# Micro.net
KiCad netlist of a schematic drawn in Altium Designer
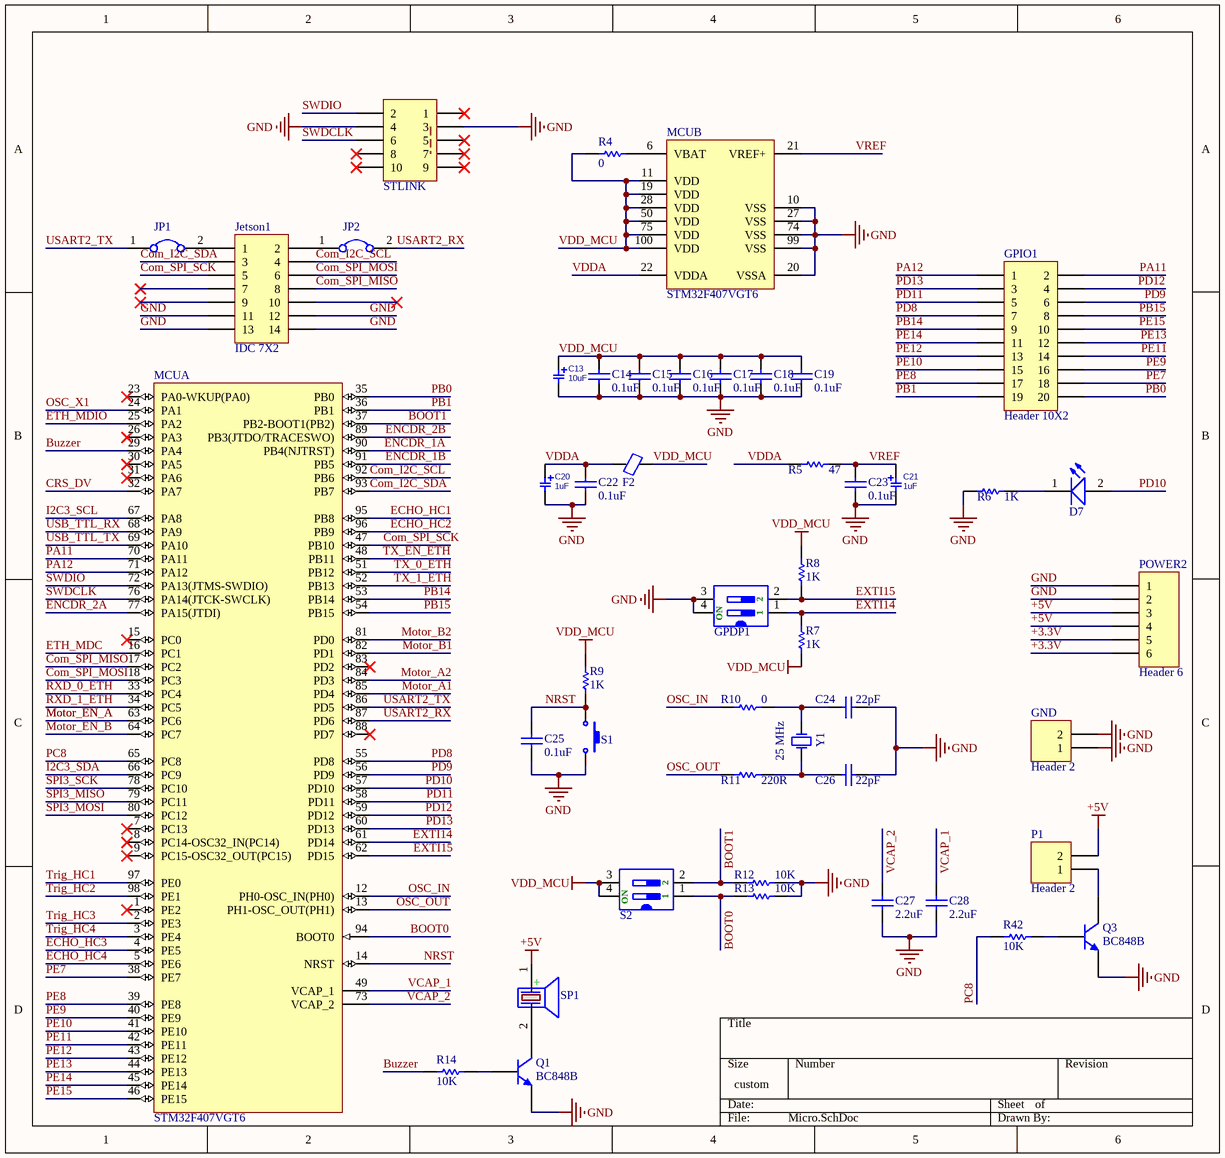
[diagram p0: Micro.SchDoc]

(export (version "E")
  (design (tool "Eeschema 10.0.6"))
  (components
    (comp (ref "C13")
      (value "10uF")
      (footprint "C_TN_6032")
      (description "CAP, SMD, TAN,")
      (libsource (lib "Passive") (part "CAP_SMD_TAN"))
    )
    (comp (ref "C14")
      (value "0.1uF")
      (footprint "CAPC3413X12N")
      (description "CAP 0805")
      (fields (field (name "DESIGNER") "Abbas Basereh"))
      (libsource (lib "Altium") (part "CAP SMD 0805"))
    )
    (comp (ref "C15")
      (value "0.1uF")
      (footprint "CAPC3413X12N")
      (description "CAP 0805")
      (fields (field (name "DESIGNER") "Abbas Basereh"))
      (libsource (lib "Altium") (part "CAP SMD 0805"))
    )
    (comp (ref "C16")
      (value "0.1uF")
      (footprint "CAPC3413X12N")
      (description "CAP 0805")
      (fields (field (name "DESIGNER") "Abbas Basereh"))
      (libsource (lib "Altium") (part "CAP SMD 0805"))
    )
    (comp (ref "C17")
      (value "0.1uF")
      (footprint "CAPC3413X12N")
      (description "CAP 0805")
      (fields (field (name "DESIGNER") "Abbas Basereh"))
      (libsource (lib "Altium") (part "CAP SMD 0805"))
    )
    (comp (ref "C18")
      (value "0.1uF")
      (footprint "CAPC3413X12N")
      (description "CAP 0805")
      (fields (field (name "DESIGNER") "Abbas Basereh"))
      (libsource (lib "Altium") (part "CAP SMD 0805"))
    )
    (comp (ref "C19")
      (value "0.1uF")
      (footprint "CAPC3413X12N")
      (description "CAP 0805")
      (fields (field (name "DESIGNER") "Abbas Basereh"))
      (libsource (lib "Altium") (part "CAP SMD 0805"))
    )
    (comp (ref "C20")
      (value "1uF")
      (footprint "C_TN_6032")
      (description "CAP, SMD, TAN,")
      (libsource (lib "Passive") (part "CAP_SMD_TAN"))
    )
    (comp (ref "C21")
      (value "1uF")
      (footprint "C_TN_6032")
      (description "CAP, SMD, TAN,")
      (libsource (lib "Passive") (part "CAP_SMD_TAN"))
    )
    (comp (ref "C22")
      (value "0.1uF")
      (footprint "CAPC3413X12N")
      (description "CAP 0805")
      (fields (field (name "DESIGNER") "Abbas Basereh"))
      (libsource (lib "Altium") (part "CAP SMD 0805"))
    )
    (comp (ref "C23")
      (value "0.1uF")
      (footprint "CAPC3413X12N")
      (description "CAP 0805")
      (fields (field (name "DESIGNER") "Abbas Basereh"))
      (libsource (lib "Altium") (part "CAP SMD 0805"))
    )
    (comp (ref "C24")
      (value "22pF")
      (footprint "CAPC3413X12N")
      (description "CAP 0805")
      (fields (field (name "DESIGNER") "Abbas Basereh"))
      (libsource (lib "Altium") (part "CAP SMD 0805"))
    )
    (comp (ref "C25")
      (value "0.1uF")
      (footprint "CAPC3413X12N")
      (description "CAP 0805")
      (fields (field (name "DESIGNER") "Abbas Basereh"))
      (libsource (lib "Altium") (part "CAP SMD 0805"))
    )
    (comp (ref "C26")
      (value "22pF")
      (footprint "CAPC3413X12N")
      (description "CAP 0805")
      (fields (field (name "DESIGNER") "Abbas Basereh"))
      (libsource (lib "Altium") (part "CAP SMD 0805"))
    )
    (comp (ref "C27")
      (value "2.2uF")
      (footprint "CAPC3413X12N")
      (description "CAP 0805")
      (fields (field (name "DESIGNER") "Abbas Basereh"))
      (libsource (lib "Altium") (part "CAP SMD 0805"))
    )
    (comp (ref "C28")
      (value "2.2uF")
      (footprint "CAPC3413X12N")
      (description "CAP 0805")
      (fields (field (name "DESIGNER") "Abbas Basereh"))
      (libsource (lib "Altium") (part "CAP SMD 0805"))
    )
    (comp (ref "D7")
      (value "LED SMD PACKAGE")
      (footprint "LED_SMD_0805")
      (description "SMD Mono-color Chip LED Waterclear")
      (fields (field (name "PART NUMBER") "150080BS75000") (field (name "PUBLISHER") "Ali Hafizi"))
      (libsource (lib "Altium") (part "LED SMD PACKAGE"))
    )
    (comp (ref "F2")
      (value "Ferrite Bead SMD")
      (footprint "FB0805")
      (fields (field (name "DESIGNER") "Ali Hafizi"))
      (libsource (lib "Altium") (part "Ferrite Bead SMD Package"))
    )
    (comp (ref "GND")
      (value "Header 2")
      (footprint "HDR1X2")
      (description "Header, 2-Pin")
      (fields (field (name "PUBLISHER") "Altium Limited"))
      (libsource (lib "Altium") (part "Header 2"))
    )
    (comp (ref "GPDP1")
      (value "SW_DIP_02")
      (footprint "SMV_DIP_CTS-219-02")
      (libsource (lib "SJ Switches") (part "SW_DIP_02"))
    )
    (comp (ref "GPIO1")
      (value "Header 10X2")
      (footprint "HDR2X10")
      (description "Header, 10-Pin, Dual row")
      (fields (field (name "PUBLISHER") "Altium Limited"))
      (libsource (lib "Altium") (part "Header 10X2"))
    )
    (comp (ref "Jetson1")
      (value "IDC 7X2")
      (footprint "IDC 7X2:IDC 7X2")
      (libsource (lib "IDC 7X2") (part "IDC 7X2"))
    )
    (comp (ref "JP1")
      (value "Jumper")
      (footprint "Jumper Small - 2.54 - GRAY")
      (libsource (lib "Altium") (part "Jumper"))
    )
    (comp (ref "JP2")
      (value "Jumper")
      (footprint "Jumper Small - 2.54 - GRAY")
      (libsource (lib "Altium") (part "Jumper"))
    )
    (comp (ref "MCU")
      (value "STM32F407VGT6")
      (footprint "STM-LQFP100_N")
      (fields (field (name "MANUFACTURER") "STMicroelectronics"))
      (libsource (lib "STMicroelectronics STM32 F4") (part "STM32F407VGT6"))
    )
    (comp (ref "P1")
      (value "Header 2")
      (footprint "HDR1X2")
      (description "Header, 2-Pin")
      (fields (field (name "PUBLISHER") "Altium Limited"))
      (libsource (lib "Altium") (part "Header 2"))
    )
    (comp (ref "POWER2")
      (value "Header 6")
      (footprint "HDR1X6")
      (description "Header, 6-Pin")
      (fields (field (name "PUBLISHER") "Altium Limited"))
      (libsource (lib "Altium") (part "Header 6"))
    )
    (comp (ref "Q1")
      (value "BC848B")
      (footprint "SOT23_L")
      (description "NPN General-purpose Transistor")
      (fields (field (name "PUBLISHER") "Abbas Basereh"))
      (libsource (lib "Altium") (part "BC848B"))
    )
    (comp (ref "Q3")
      (value "BC848B")
      (footprint "SOT23_L")
      (description "NPN General-purpose Transistor")
      (fields (field (name "PUBLISHER") "Abbas Basereh"))
      (libsource (lib "Altium") (part "BC848B"))
    )
    (comp (ref "R4")
      (value "0")
      (footprint "RESC3413X04N")
      (description "RES 0805")
      (fields (field (name "DESIGNER") "Abbas Basereh"))
      (libsource (lib "Altium") (part "RES 0805 0.125W"))
    )
    (comp (ref "R5")
      (value "47")
      (footprint "RESC3413X04N")
      (description "RES 0805")
      (fields (field (name "DESIGNER") "Abbas Basereh"))
      (libsource (lib "Altium") (part "RES 0805 0.125W"))
    )
    (comp (ref "R6")
      (value "1K")
      (footprint "RESC3413X04N")
      (description "RES 0805")
      (fields (field (name "DESIGNER") "Abbas Basereh"))
      (libsource (lib "Altium") (part "RES 0805 0.125W"))
    )
    (comp (ref "R7")
      (value "1K")
      (footprint "RESC3413X04N")
      (description "RES 0805")
      (fields (field (name "DESIGNER") "Abbas Basereh"))
      (libsource (lib "Altium") (part "RES 0805 0.125W"))
    )
    (comp (ref "R8")
      (value "1K")
      (footprint "RESC3413X04N")
      (description "RES 0805")
      (fields (field (name "DESIGNER") "Abbas Basereh"))
      (libsource (lib "Altium") (part "RES 0805 0.125W"))
    )
    (comp (ref "R9")
      (value "1K")
      (footprint "RESC3413X04N")
      (description "RES 0805")
      (fields (field (name "DESIGNER") "Abbas Basereh"))
      (libsource (lib "Altium") (part "RES 0805 0.125W"))
    )
    (comp (ref "R10")
      (value "0")
      (footprint "RESC3413X04N")
      (description "RES 0805")
      (fields (field (name "DESIGNER") "Abbas Basereh"))
      (libsource (lib "Altium") (part "RES 0805 0.125W"))
    )
    (comp (ref "R11")
      (value "220R")
      (footprint "RESC3413X04N")
      (description "RES 0805")
      (fields (field (name "DESIGNER") "Abbas Basereh"))
      (libsource (lib "Altium") (part "RES 0805 0.125W"))
    )
    (comp (ref "R12")
      (value "10K")
      (footprint "RESC3413X04N")
      (description "RES 0805")
      (fields (field (name "DESIGNER") "Abbas Basereh"))
      (libsource (lib "Altium") (part "RES 0805 0.125W"))
    )
    (comp (ref "R13")
      (value "10K")
      (footprint "RESC3413X04N")
      (description "RES 0805")
      (fields (field (name "DESIGNER") "Abbas Basereh"))
      (libsource (lib "Altium") (part "RES 0805 0.125W"))
    )
    (comp (ref "R14")
      (value "10K")
      (footprint "RES0805_(2012X06L)")
      (description "TOTAL SMD RESISTOR PACK")
      (fields (field (name "DESIGNER") "Abbas Basereh"))
      (libsource (lib "Altium") (part "RES SMD PACKAGE"))
    )
    (comp (ref "R42")
      (value "10K")
      (footprint "RES0805_(2012X06L)")
      (description "TOTAL SMD RESISTOR PACK")
      (fields (field (name "DESIGNER") "Abbas Basereh"))
      (libsource (lib "Altium") (part "RES SMD PACKAGE"))
    )
    (comp (ref "S1")
      (value "Switch PB")
      (footprint "SW-PB")
      (description "Push Button Switch")
      (libsource (lib "Altium") (part "Switch PB"))
    )
    (comp (ref "S2")
      (value "SW_DIP_02")
      (footprint "SMV_DIP_CTS-219-02")
      (libsource (lib "SJ Switches") (part "SW_DIP_02"))
    )
    (comp (ref "SP1")
      (value "~")
      (footprint "BUZZER 7.62mm DC")
      (description "PIEZO BUZZER ACTIVE")
      (fields (field (name "DESIGNER") "Abbas Basereh") (field (name "PUBLISHER") "Abbas Basereh"))
      (libsource (lib "Altium") (part "PIEZO BUZZER"))
    )
    (comp (ref "STLINK")
      (value "CONNECTOR_IDC_5X2")
      (footprint "IDC2.54-10PIN")
      (description "IDC, 5-Pin, Dual row")
      (fields
        (field (name "MANUFACTURER") "CHINA")
        (field (name "PUBLISHER") "ABBAS BASEREH")
        (field (name "DESIGNER") "ABBAS BASEREH")
      )
      (libsource (lib "Altium") (part "IDC 5X2"))
    )
    (comp (ref "Y1")
      (value "25 MHz")
      (footprint "Crystal SMD")
      (description "XTAL Crystal")
      (fields (field (name "DESIGNER") "ABBAS BASEREH"))
      (libsource (lib "Altium") (part "XTAL"))
    )
  )
  (nets
    (net (code "1") (name "+5V") (class "Default")
      (node (ref "P1") (pin "2") (pinfunction "2_2") (pintype "passive"))
      (node (ref "POWER2") (pin "3") (pinfunction "3_3") (pintype "passive"))
      (node (ref "POWER2") (pin "4") (pinfunction "4_4") (pintype "passive"))
      (node (ref "SP1") (pin "1") (pinfunction "+_1") (pintype "passive"))
    )
    (net (code "2") (name "/+3.3V") (class "Default")
      (node (ref "POWER2") (pin "5") (pinfunction "5_5") (pintype "passive"))
      (node (ref "POWER2") (pin "6") (pinfunction "6_6") (pintype "passive"))
    )
    (net (code "3") (name "/BOOT0") (class "Default")
      (node (ref "MCU") (pin "94") (pinfunction "BOOT0_94") (pintype "input"))
      (node (ref "R13") (pin "1") (pinfunction "1_1") (pintype "passive"))
      (node (ref "S2") (pin "1") (pinfunction "1_1") (pintype "passive"))
    )
    (net (code "4") (name "/BOOT1") (class "Default")
      (node (ref "MCU") (pin "37") (pinfunction "PB2-BOOT1(PB2)_37") (pintype "bidirectional"))
      (node (ref "R12") (pin "1") (pinfunction "1_1") (pintype "passive"))
      (node (ref "S2") (pin "2") (pinfunction "2_2") (pintype "passive"))
    )
    (net (code "5") (name "/Buzzer") (class "Default")
      (node (ref "MCU") (pin "29") (pinfunction "PA4_29") (pintype "bidirectional"))
      (node (ref "R14") (pin "1") (pinfunction "1_1") (pintype "passive"))
    )
    (net (code "6") (name "/CRS_DV") (class "Default")
      (node (ref "MCU") (pin "32") (pinfunction "PA7_32") (pintype "bidirectional"))
    )
    (net (code "7") (name "/Com_I2C_SCL") (class "Default")
      (node (ref "Jetson1") (pin "4") (pinfunction "4_4") (pintype "passive"))
      (node (ref "MCU") (pin "92") (pinfunction "PB6_92") (pintype "bidirectional"))
    )
    (net (code "8") (name "/Com_I2C_SDA") (class "Default")
      (node (ref "Jetson1") (pin "3") (pinfunction "3_3") (pintype "passive"))
      (node (ref "MCU") (pin "93") (pinfunction "PB7_93") (pintype "bidirectional"))
    )
    (net (code "9") (name "/Com_SPI_MISO") (class "Default")
      (node (ref "Jetson1") (pin "8") (pinfunction "8_8") (pintype "passive"))
      (node (ref "MCU") (pin "17") (pinfunction "PC2_17") (pintype "bidirectional"))
    )
    (net (code "10") (name "/Com_SPI_MOSI") (class "Default")
      (node (ref "Jetson1") (pin "6") (pinfunction "6_6") (pintype "passive"))
      (node (ref "MCU") (pin "18") (pinfunction "PC3_18") (pintype "bidirectional"))
    )
    (net (code "11") (name "/Com_SPI_SCK") (class "Default")
      (node (ref "Jetson1") (pin "5") (pinfunction "5_5") (pintype "passive"))
      (node (ref "MCU") (pin "47") (pinfunction "PB10_47") (pintype "bidirectional"))
    )
    (net (code "12") (name "/ECHO_HC1") (class "Default")
      (node (ref "MCU") (pin "95") (pinfunction "PB8_95") (pintype "bidirectional"))
    )
    (net (code "13") (name "/ECHO_HC2") (class "Default")
      (node (ref "MCU") (pin "96") (pinfunction "PB9_96") (pintype "bidirectional"))
    )
    (net (code "14") (name "/ECHO_HC3") (class "Default")
      (node (ref "MCU") (pin "4") (pinfunction "PE5_4") (pintype "bidirectional"))
    )
    (net (code "15") (name "/ECHO_HC4") (class "Default")
      (node (ref "MCU") (pin "5") (pinfunction "PE6_5") (pintype "bidirectional"))
    )
    (net (code "16") (name "/ENCDR_1A") (class "Default")
      (node (ref "MCU") (pin "90") (pinfunction "PB4(NJTRST)_90") (pintype "bidirectional"))
    )
    (net (code "17") (name "/ENCDR_1B") (class "Default")
      (node (ref "MCU") (pin "91") (pinfunction "PB5_91") (pintype "bidirectional"))
    )
    (net (code "18") (name "/ENCDR_2A") (class "Default")
      (node (ref "MCU") (pin "77") (pinfunction "PA15(JTDI)_77") (pintype "bidirectional"))
    )
    (net (code "19") (name "/ENCDR_2B") (class "Default")
      (node (ref "MCU") (pin "89") (pinfunction "PB3(JTDO/TRACESWO)_89") (pintype "bidirectional"))
    )
    (net (code "20") (name "/ETH_MDC") (class "Default")
      (node (ref "MCU") (pin "16") (pinfunction "PC1_16") (pintype "bidirectional"))
    )
    (net (code "21") (name "/ETH_MDIO") (class "Default")
      (node (ref "MCU") (pin "25") (pinfunction "PA2_25") (pintype "bidirectional"))
    )
    (net (code "22") (name "/EXTI14") (class "Default")
      (node (ref "GPDP1") (pin "1") (pinfunction "1_1") (pintype "passive"))
      (node (ref "MCU") (pin "61") (pinfunction "PD14_61") (pintype "bidirectional"))
      (node (ref "R7") (pin "2") (pinfunction "2_2") (pintype "passive"))
    )
    (net (code "23") (name "/EXTI15") (class "Default")
      (node (ref "GPDP1") (pin "2") (pinfunction "2_2") (pintype "passive"))
      (node (ref "MCU") (pin "62") (pinfunction "PD15_62") (pintype "bidirectional"))
      (node (ref "R8") (pin "2") (pinfunction "2_2") (pintype "passive"))
    )
    (net (code "24") (name "/I2C3_SCL") (class "Default")
      (node (ref "MCU") (pin "67") (pinfunction "PA8_67") (pintype "bidirectional"))
    )
    (net (code "25") (name "/I2C3_SDA") (class "Default")
      (node (ref "MCU") (pin "66") (pinfunction "PC9_66") (pintype "bidirectional"))
    )
    (net (code "26") (name "/Motor_A1") (class "Default")
      (node (ref "MCU") (pin "85") (pinfunction "PD4_85") (pintype "bidirectional"))
    )
    (net (code "27") (name "/Motor_A2") (class "Default")
      (node (ref "MCU") (pin "84") (pinfunction "PD3_84") (pintype "bidirectional"))
    )
    (net (code "28") (name "/Motor_B1") (class "Default")
      (node (ref "MCU") (pin "82") (pinfunction "PD1_82") (pintype "bidirectional"))
    )
    (net (code "29") (name "/Motor_B2") (class "Default")
      (node (ref "MCU") (pin "81") (pinfunction "PD0_81") (pintype "bidirectional"))
    )
    (net (code "30") (name "/Motor_EN_A") (class "Default")
      (node (ref "MCU") (pin "63") (pinfunction "PC6_63") (pintype "bidirectional"))
    )
    (net (code "31") (name "/Motor_EN_B") (class "Default")
      (node (ref "MCU") (pin "64") (pinfunction "PC7_64") (pintype "bidirectional"))
    )
    (net (code "32") (name "/NRST") (class "Default")
      (node (ref "C25") (pin "2") (pinfunction "2_2") (pintype "passive"))
      (node (ref "MCU") (pin "14") (pinfunction "NRST_14") (pintype "bidirectional"))
      (node (ref "R9") (pin "1") (pinfunction "1_1") (pintype "passive"))
      (node (ref "S1") (pin "1") (pinfunction "1_1") (pintype "passive"))
    )
    (net (code "33") (name "/OSC_IN") (class "Default")
      (node (ref "MCU") (pin "12") (pinfunction "PH0-OSC_IN(PH0)_12") (pintype "bidirectional"))
      (node (ref "R10") (pin "1") (pinfunction "1_1") (pintype "passive"))
    )
    (net (code "34") (name "/OSC_OUT") (class "Default")
      (node (ref "MCU") (pin "13") (pinfunction "PH1-OSC_OUT(PH1)_13") (pintype "bidirectional"))
      (node (ref "R11") (pin "1") (pinfunction "1_1") (pintype "passive"))
    )
    (net (code "35") (name "/OSC_X1") (class "Default")
      (node (ref "MCU") (pin "24") (pinfunction "PA1_24") (pintype "bidirectional"))
    )
    (net (code "36") (name "/PA11") (class "Default")
      (node (ref "GPIO1") (pin "2") (pinfunction "2_2") (pintype "passive"))
      (node (ref "MCU") (pin "70") (pinfunction "PA11_70") (pintype "bidirectional"))
    )
    (net (code "37") (name "/PA12") (class "Default")
      (node (ref "GPIO1") (pin "1") (pinfunction "1_1") (pintype "passive"))
      (node (ref "MCU") (pin "71") (pinfunction "PA12_71") (pintype "bidirectional"))
    )
    (net (code "38") (name "/PB0") (class "Default")
      (node (ref "GPIO1") (pin "20") (pinfunction "20_20") (pintype "passive"))
      (node (ref "MCU") (pin "35") (pinfunction "PB0_35") (pintype "bidirectional"))
    )
    (net (code "39") (name "/PB1") (class "Default")
      (node (ref "GPIO1") (pin "19") (pinfunction "19_19") (pintype "passive"))
      (node (ref "MCU") (pin "36") (pinfunction "PB1_36") (pintype "bidirectional"))
    )
    (net (code "40") (name "/PB14") (class "Default")
      (node (ref "GPIO1") (pin "9") (pinfunction "9_9") (pintype "passive"))
      (node (ref "MCU") (pin "53") (pinfunction "PB14_53") (pintype "bidirectional"))
    )
    (net (code "41") (name "/PB15") (class "Default")
      (node (ref "GPIO1") (pin "8") (pinfunction "8_8") (pintype "passive"))
      (node (ref "MCU") (pin "54") (pinfunction "PB15_54") (pintype "bidirectional"))
    )
    (net (code "42") (name "/PC8") (class "Default")
      (node (ref "MCU") (pin "65") (pinfunction "PC8_65") (pintype "bidirectional"))
      (node (ref "R42") (pin "1") (pinfunction "1_1") (pintype "passive"))
    )
    (net (code "43") (name "/PD8") (class "Default")
      (node (ref "GPIO1") (pin "7") (pinfunction "7_7") (pintype "passive"))
      (node (ref "MCU") (pin "55") (pinfunction "PD8_55") (pintype "bidirectional"))
    )
    (net (code "44") (name "/PD9") (class "Default")
      (node (ref "GPIO1") (pin "6") (pinfunction "6_6") (pintype "passive"))
      (node (ref "MCU") (pin "56") (pinfunction "PD9_56") (pintype "bidirectional"))
    )
    (net (code "45") (name "/PD10") (class "Default")
      (node (ref "D7") (pin "2") (pinfunction "A_2") (pintype "passive"))
      (node (ref "MCU") (pin "57") (pinfunction "PD10_57") (pintype "bidirectional"))
    )
    (net (code "46") (name "/PD11") (class "Default")
      (node (ref "GPIO1") (pin "5") (pinfunction "5_5") (pintype "passive"))
      (node (ref "MCU") (pin "58") (pinfunction "PD11_58") (pintype "bidirectional"))
    )
    (net (code "47") (name "/PD12") (class "Default")
      (node (ref "GPIO1") (pin "4") (pinfunction "4_4") (pintype "passive"))
      (node (ref "MCU") (pin "59") (pinfunction "PD12_59") (pintype "bidirectional"))
    )
    (net (code "48") (name "/PD13") (class "Default")
      (node (ref "GPIO1") (pin "3") (pinfunction "3_3") (pintype "passive"))
      (node (ref "MCU") (pin "60") (pinfunction "PD13_60") (pintype "bidirectional"))
    )
    (net (code "49") (name "/PE7") (class "Default")
      (node (ref "GPIO1") (pin "18") (pinfunction "18_18") (pintype "passive"))
      (node (ref "MCU") (pin "38") (pinfunction "PE7_38") (pintype "bidirectional"))
    )
    (net (code "50") (name "/PE8") (class "Default")
      (node (ref "GPIO1") (pin "17") (pinfunction "17_17") (pintype "passive"))
      (node (ref "MCU") (pin "39") (pinfunction "PE8_39") (pintype "bidirectional"))
    )
    (net (code "51") (name "/PE9") (class "Default")
      (node (ref "GPIO1") (pin "16") (pinfunction "16_16") (pintype "passive"))
      (node (ref "MCU") (pin "40") (pinfunction "PE9_40") (pintype "bidirectional"))
    )
    (net (code "52") (name "/PE10") (class "Default")
      (node (ref "GPIO1") (pin "15") (pinfunction "15_15") (pintype "passive"))
      (node (ref "MCU") (pin "41") (pinfunction "PE10_41") (pintype "bidirectional"))
    )
    (net (code "53") (name "/PE11") (class "Default")
      (node (ref "GPIO1") (pin "14") (pinfunction "14_14") (pintype "passive"))
      (node (ref "MCU") (pin "42") (pinfunction "PE11_42") (pintype "bidirectional"))
    )
    (net (code "54") (name "/PE12") (class "Default")
      (node (ref "GPIO1") (pin "13") (pinfunction "13_13") (pintype "passive"))
      (node (ref "MCU") (pin "43") (pinfunction "PE12_43") (pintype "bidirectional"))
    )
    (net (code "55") (name "/PE13") (class "Default")
      (node (ref "GPIO1") (pin "12") (pinfunction "12_12") (pintype "passive"))
      (node (ref "MCU") (pin "44") (pinfunction "PE13_44") (pintype "bidirectional"))
    )
    (net (code "56") (name "/PE14") (class "Default")
      (node (ref "GPIO1") (pin "11") (pinfunction "11_11") (pintype "passive"))
      (node (ref "MCU") (pin "45") (pinfunction "PE14_45") (pintype "bidirectional"))
    )
    (net (code "57") (name "/PE15") (class "Default")
      (node (ref "GPIO1") (pin "10") (pinfunction "10_10") (pintype "passive"))
      (node (ref "MCU") (pin "46") (pinfunction "PE15_46") (pintype "bidirectional"))
    )
    (net (code "58") (name "/RXD_0_ETH") (class "Default")
      (node (ref "MCU") (pin "33") (pinfunction "PC4_33") (pintype "bidirectional"))
    )
    (net (code "59") (name "/RXD_1_ETH") (class "Default")
      (node (ref "MCU") (pin "34") (pinfunction "PC5_34") (pintype "bidirectional"))
    )
    (net (code "60") (name "/SPI3_MISO") (class "Default")
      (node (ref "MCU") (pin "79") (pinfunction "PC11_79") (pintype "bidirectional"))
    )
    (net (code "61") (name "/SPI3_MOSI") (class "Default")
      (node (ref "MCU") (pin "80") (pinfunction "PC12_80") (pintype "bidirectional"))
    )
    (net (code "62") (name "/SPI3_SCK") (class "Default")
      (node (ref "MCU") (pin "78") (pinfunction "PC10_78") (pintype "bidirectional"))
    )
    (net (code "63") (name "/SWDCLK") (class "Default")
      (node (ref "MCU") (pin "76") (pinfunction "PA14(JTCK-SWCLK)_76") (pintype "bidirectional"))
      (node (ref "STLINK") (pin "6") (pinfunction "6_6") (pintype "passive"))
    )
    (net (code "64") (name "/SWDIO") (class "Default")
      (node (ref "MCU") (pin "72") (pinfunction "PA13(JTMS-SWDIO)_72") (pintype "bidirectional"))
      (node (ref "STLINK") (pin "2") (pinfunction "2_2") (pintype "passive"))
    )
    (net (code "65") (name "/TX_0_ETH") (class "Default")
      (node (ref "MCU") (pin "51") (pinfunction "PB12_51") (pintype "bidirectional"))
    )
    (net (code "66") (name "/TX_1_ETH") (class "Default")
      (node (ref "MCU") (pin "52") (pinfunction "PB13_52") (pintype "bidirectional"))
    )
    (net (code "67") (name "/TX_EN_ETH") (class "Default")
      (node (ref "MCU") (pin "48") (pinfunction "PB11_48") (pintype "bidirectional"))
    )
    (net (code "68") (name "/Trig_HC1") (class "Default")
      (node (ref "MCU") (pin "97") (pinfunction "PE0_97") (pintype "bidirectional"))
    )
    (net (code "69") (name "/Trig_HC2") (class "Default")
      (node (ref "MCU") (pin "98") (pinfunction "PE1_98") (pintype "bidirectional"))
    )
    (net (code "70") (name "/Trig_HC3") (class "Default")
      (node (ref "MCU") (pin "2") (pinfunction "PE3_2") (pintype "bidirectional"))
    )
    (net (code "71") (name "/Trig_HC4") (class "Default")
      (node (ref "MCU") (pin "3") (pinfunction "PE4_3") (pintype "bidirectional"))
    )
    (net (code "72") (name "/USART2_RX") (class "Default")
      (node (ref "JP2") (pin "2") (pinfunction "2_2") (pintype "passive"))
      (node (ref "MCU") (pin "87") (pinfunction "PD6_87") (pintype "bidirectional"))
    )
    (net (code "73") (name "/USART2_TX") (class "Default")
      (node (ref "JP1") (pin "1") (pinfunction "1_1") (pintype "passive"))
      (node (ref "MCU") (pin "86") (pinfunction "PD5_86") (pintype "bidirectional"))
    )
    (net (code "74") (name "/USB_TTL_RX") (class "Default")
      (node (ref "MCU") (pin "68") (pinfunction "PA9_68") (pintype "bidirectional"))
    )
    (net (code "75") (name "/USB_TTL_TX") (class "Default")
      (node (ref "MCU") (pin "69") (pinfunction "PA10_69") (pintype "bidirectional"))
    )
    (net (code "76") (name "/VCAP_1") (class "Default")
      (node (ref "C28") (pin "2") (pinfunction "2_2") (pintype "passive"))
      (node (ref "MCU") (pin "49") (pinfunction "VCAP_1_49") (pintype "power_in"))
    )
    (net (code "77") (name "/VCAP_2") (class "Default")
      (node (ref "C27") (pin "2") (pinfunction "2_2") (pintype "passive"))
      (node (ref "MCU") (pin "73") (pinfunction "VCAP_2_73") (pintype "power_in"))
    )
    (net (code "78") (name "/VDDA") (class "Default")
      (node (ref "C20") (pin "1") (pinfunction "1_1") (pintype "passive"))
      (node (ref "C22") (pin "2") (pinfunction "2_2") (pintype "passive"))
      (node (ref "F2") (pin "1") (pinfunction "1_1") (pintype "passive"))
      (node (ref "MCU") (pin "22") (pinfunction "VDDA_22") (pintype "power_in"))
      (node (ref "R5") (pin "1") (pinfunction "1_1") (pintype "passive"))
    )
    (net (code "79") (name "/VREF") (class "Default")
      (node (ref "C21") (pin "1") (pinfunction "1_1") (pintype "passive"))
      (node (ref "C23") (pin "2") (pinfunction "2_2") (pintype "passive"))
      (node (ref "MCU") (pin "21") (pinfunction "VREF+_21") (pintype "power_in"))
      (node (ref "R5") (pin "2") (pinfunction "2_2") (pintype "passive"))
    )
    (net (code "80") (name "GND") (class "Default")
      (node (ref "C13") (pin "2") (pinfunction "2_2") (pintype "passive"))
      (node (ref "C14") (pin "1") (pinfunction "1_1") (pintype "passive"))
      (node (ref "C15") (pin "1") (pinfunction "1_1") (pintype "passive"))
      (node (ref "C16") (pin "1") (pinfunction "1_1") (pintype "passive"))
      (node (ref "C17") (pin "1") (pinfunction "1_1") (pintype "passive"))
      (node (ref "C18") (pin "1") (pinfunction "1_1") (pintype "passive"))
      (node (ref "C19") (pin "1") (pinfunction "1_1") (pintype "passive"))
      (node (ref "C20") (pin "2") (pinfunction "2_2") (pintype "passive"))
      (node (ref "C21") (pin "2") (pinfunction "2_2") (pintype "passive"))
      (node (ref "C22") (pin "1") (pinfunction "1_1") (pintype "passive"))
      (node (ref "C23") (pin "1") (pinfunction "1_1") (pintype "passive"))
      (node (ref "C24") (pin "1") (pinfunction "1_1") (pintype "passive"))
      (node (ref "C25") (pin "1") (pinfunction "1_1") (pintype "passive"))
      (node (ref "C26") (pin "1") (pinfunction "1_1") (pintype "passive"))
      (node (ref "C27") (pin "1") (pinfunction "1_1") (pintype "passive"))
      (node (ref "C28") (pin "1") (pinfunction "1_1") (pintype "passive"))
      (node (ref "GND") (pin "1") (pinfunction "1_1") (pintype "passive"))
      (node (ref "GND") (pin "2") (pinfunction "2_2") (pintype "passive"))
      (node (ref "GPDP1") (pin "3") (pinfunction "3_3") (pintype "passive"))
      (node (ref "GPDP1") (pin "4") (pinfunction "4_4") (pintype "passive"))
      (node (ref "Jetson1") (pin "11") (pinfunction "11_11") (pintype "passive"))
      (node (ref "Jetson1") (pin "12") (pinfunction "12_12") (pintype "passive"))
      (node (ref "Jetson1") (pin "13") (pinfunction "13_13") (pintype "passive"))
      (node (ref "Jetson1") (pin "14") (pinfunction "14_14") (pintype "passive"))
      (node (ref "MCU") (pin "10") (pinfunction "VSS_10") (pintype "power_in"))
      (node (ref "MCU") (pin "20") (pinfunction "VSSA_20") (pintype "power_in"))
      (node (ref "MCU") (pin "27") (pinfunction "VSS_27") (pintype "power_in"))
      (node (ref "MCU") (pin "74") (pinfunction "VSS_74") (pintype "power_in"))
      (node (ref "MCU") (pin "99") (pinfunction "VSS_99") (pintype "power_in"))
      (node (ref "POWER2") (pin "1") (pinfunction "1_1") (pintype "passive"))
      (node (ref "POWER2") (pin "2") (pinfunction "2_2") (pintype "passive"))
      (node (ref "Q1") (pin "2") (pinfunction "E_2") (pintype "passive"))
      (node (ref "Q3") (pin "2") (pinfunction "E_2") (pintype "passive"))
      (node (ref "R12") (pin "2") (pinfunction "2_2") (pintype "passive"))
      (node (ref "R13") (pin "2") (pinfunction "2_2") (pintype "passive"))
      (node (ref "R6") (pin "1") (pinfunction "1_1") (pintype "passive"))
      (node (ref "S1") (pin "2") (pinfunction "2_2") (pintype "passive"))
      (node (ref "STLINK") (pin "3") (pinfunction "3_3") (pintype "passive"))
      (node (ref "STLINK") (pin "4") (pinfunction "4_4") (pintype "passive"))
    )
    (net (code "81") (name "Net-(D7-K)") (class "Default")
      (node (ref "D7") (pin "1") (pinfunction "K_1") (pintype "passive"))
      (node (ref "R6") (pin "2") (pinfunction "2_2") (pintype "passive"))
    )
    (net (code "82") (name "Net-(JP1-Pad2)") (class "Default")
      (node (ref "JP1") (pin "2") (pinfunction "2_2") (pintype "passive"))
      (node (ref "Jetson1") (pin "1") (pinfunction "1_1") (pintype "passive"))
    )
    (net (code "83") (name "Net-(JP2-Pad1)") (class "Default")
      (node (ref "JP2") (pin "1") (pinfunction "1_1") (pintype "passive"))
      (node (ref "Jetson1") (pin "2") (pinfunction "2_2") (pintype "passive"))
    )
    (net (code "84") (name "Net-(MCUB-VBAT)") (class "Default")
      (node (ref "MCU") (pin "6") (pinfunction "VBAT_6") (pintype "power_in"))
      (node (ref "R4") (pin "2") (pinfunction "2_2") (pintype "passive"))
    )
    (net (code "85") (name "Net-(Q1-B)") (class "Default")
      (node (ref "Q1") (pin "1") (pinfunction "B_1") (pintype "passive"))
      (node (ref "R14") (pin "2") (pinfunction "2_2") (pintype "passive"))
    )
    (net (code "86") (name "Net-(Q1-C)") (class "Default")
      (node (ref "Q1") (pin "3") (pinfunction "C_3") (pintype "passive"))
      (node (ref "SP1") (pin "2") (pinfunction "-_2") (pintype "passive"))
    )
    (net (code "87") (name "Net-(Q3-B)") (class "Default")
      (node (ref "Q3") (pin "1") (pinfunction "B_1") (pintype "passive"))
      (node (ref "R42") (pin "2") (pinfunction "2_2") (pintype "passive"))
    )
    (net (code "88") (name "Net-(Q3-C)") (class "Default")
      (node (ref "P1") (pin "1") (pinfunction "1_1") (pintype "passive"))
      (node (ref "Q3") (pin "3") (pinfunction "C_3") (pintype "passive"))
    )
    (net (code "89") (name "Net-(Y1-OSC1)") (class "Default")
      (node (ref "C26") (pin "2") (pinfunction "2_2") (pintype "passive"))
      (node (ref "R11") (pin "2") (pinfunction "2_2") (pintype "passive"))
      (node (ref "Y1") (pin "1") (pinfunction "OSC1_1") (pintype "passive"))
    )
    (net (code "90") (name "Net-(Y1-OSC2)") (class "Default")
      (node (ref "C24") (pin "2") (pinfunction "2_2") (pintype "passive"))
      (node (ref "R10") (pin "2") (pinfunction "2_2") (pintype "passive"))
      (node (ref "Y1") (pin "2") (pinfunction "OSC2_2") (pintype "passive"))
    )
    (net (code "91") (name "VDD_MCU") (class "Default")
      (node (ref "C13") (pin "1") (pinfunction "1_1") (pintype "passive"))
      (node (ref "C14") (pin "2") (pinfunction "2_2") (pintype "passive"))
      (node (ref "C15") (pin "2") (pinfunction "2_2") (pintype "passive"))
      (node (ref "C16") (pin "2") (pinfunction "2_2") (pintype "passive"))
      (node (ref "C17") (pin "2") (pinfunction "2_2") (pintype "passive"))
      (node (ref "C18") (pin "2") (pinfunction "2_2") (pintype "passive"))
      (node (ref "C19") (pin "2") (pinfunction "2_2") (pintype "passive"))
      (node (ref "F2") (pin "2") (pinfunction "2_2") (pintype "passive"))
      (node (ref "MCU") (pin "100") (pinfunction "VDD_100") (pintype "power_in"))
      (node (ref "MCU") (pin "11") (pinfunction "VDD_11") (pintype "power_in"))
      (node (ref "MCU") (pin "19") (pinfunction "VDD_19") (pintype "power_in"))
      (node (ref "MCU") (pin "28") (pinfunction "VDD_28") (pintype "power_in"))
      (node (ref "MCU") (pin "50") (pinfunction "VDD_50") (pintype "power_in"))
      (node (ref "MCU") (pin "75") (pinfunction "VDD_75") (pintype "power_in"))
      (node (ref "R4") (pin "1") (pinfunction "1_1") (pintype "passive"))
      (node (ref "R7") (pin "1") (pinfunction "1_1") (pintype "passive"))
      (node (ref "R8") (pin "1") (pinfunction "1_1") (pintype "passive"))
      (node (ref "R9") (pin "2") (pinfunction "2_2") (pintype "passive"))
      (node (ref "S2") (pin "3") (pinfunction "3_3") (pintype "passive"))
      (node (ref "S2") (pin "4") (pinfunction "4_4") (pintype "passive"))
    )
    (net (code "92") (name "unconnected-(Jetson1-Pad7)") (class "Default")
      (node (ref "Jetson1") (pin "7") (pinfunction "7_7") (pintype "passive+no_connect"))
    )
    (net (code "93") (name "unconnected-(Jetson1-Pad9)") (class "Default")
      (node (ref "Jetson1") (pin "9") (pinfunction "9_9") (pintype "passive+no_connect"))
    )
    (net (code "94") (name "unconnected-(Jetson1-Pad10)") (class "Default")
      (node (ref "Jetson1") (pin "10") (pinfunction "10_10") (pintype "passive+no_connect"))
    )
    (net (code "95") (name "unconnected-(MCUA-PA0-WKUP(PA0)-Pad23)") (class "Default")
      (node (ref "MCU") (pin "23") (pinfunction "PA0-WKUP(PA0)_23") (pintype "bidirectional+no_connect"))
    )
    (net (code "96") (name "unconnected-(MCUA-PA3-Pad26)") (class "Default")
      (node (ref "MCU") (pin "26") (pinfunction "PA3_26") (pintype "bidirectional+no_connect"))
    )
    (net (code "97") (name "unconnected-(MCUA-PA5-Pad30)") (class "Default")
      (node (ref "MCU") (pin "30") (pinfunction "PA5_30") (pintype "bidirectional+no_connect"))
    )
    (net (code "98") (name "unconnected-(MCUA-PA6-Pad31)") (class "Default")
      (node (ref "MCU") (pin "31") (pinfunction "PA6_31") (pintype "bidirectional+no_connect"))
    )
    (net (code "99") (name "unconnected-(MCUA-PC0-Pad15)") (class "Default")
      (node (ref "MCU") (pin "15") (pinfunction "PC0_15") (pintype "bidirectional+no_connect"))
    )
    (net (code "100") (name "unconnected-(MCUA-PC13-Pad7)") (class "Default")
      (node (ref "MCU") (pin "7") (pinfunction "PC13_7") (pintype "bidirectional+no_connect"))
    )
    (net (code "101") (name "unconnected-(MCUA-PC14-OSC32_IN(PC14)-Pad8)") (class "Default")
      (node (ref "MCU") (pin "8") (pinfunction "PC14-OSC32_IN(PC14)_8") (pintype "bidirectional+no_connect"))
    )
    (net (code "102") (name "unconnected-(MCUA-PC15-OSC32_OUT(PC15)-Pad9)") (class "Default")
      (node (ref "MCU") (pin "9") (pinfunction "PC15-OSC32_OUT(PC15)_9") (pintype "bidirectional+no_connect"))
    )
    (net (code "103") (name "unconnected-(MCUA-PD2-Pad83)") (class "Default")
      (node (ref "MCU") (pin "83") (pinfunction "PD2_83") (pintype "bidirectional+no_connect"))
    )
    (net (code "104") (name "unconnected-(MCUA-PD7-Pad88)") (class "Default")
      (node (ref "MCU") (pin "88") (pinfunction "PD7_88") (pintype "bidirectional+no_connect"))
    )
    (net (code "105") (name "unconnected-(MCUA-PE2-Pad1)") (class "Default")
      (node (ref "MCU") (pin "1") (pinfunction "PE2_1") (pintype "bidirectional+no_connect"))
    )
    (net (code "106") (name "unconnected-(STLINK-Pad1)") (class "Default")
      (node (ref "STLINK") (pin "1") (pinfunction "1_1") (pintype "passive+no_connect"))
    )
    (net (code "107") (name "unconnected-(STLINK-Pad5)") (class "Default")
      (node (ref "STLINK") (pin "5") (pinfunction "5_5") (pintype "passive+no_connect"))
    )
    (net (code "108") (name "unconnected-(STLINK-Pad7)") (class "Default")
      (node (ref "STLINK") (pin "7") (pinfunction "7_7") (pintype "passive+no_connect"))
    )
    (net (code "109") (name "unconnected-(STLINK-Pad8)") (class "Default")
      (node (ref "STLINK") (pin "8") (pinfunction "8_8") (pintype "passive+no_connect"))
    )
    (net (code "110") (name "unconnected-(STLINK-Pad9)") (class "Default")
      (node (ref "STLINK") (pin "9") (pinfunction "9_9") (pintype "passive+no_connect"))
    )
    (net (code "111") (name "unconnected-(STLINK-Pad10)") (class "Default")
      (node (ref "STLINK") (pin "10") (pinfunction "10_10") (pintype "passive+no_connect"))
    )
  )
)
